# piskac_pan.net
KiCad netlist of a schematic drawn in EAGLE
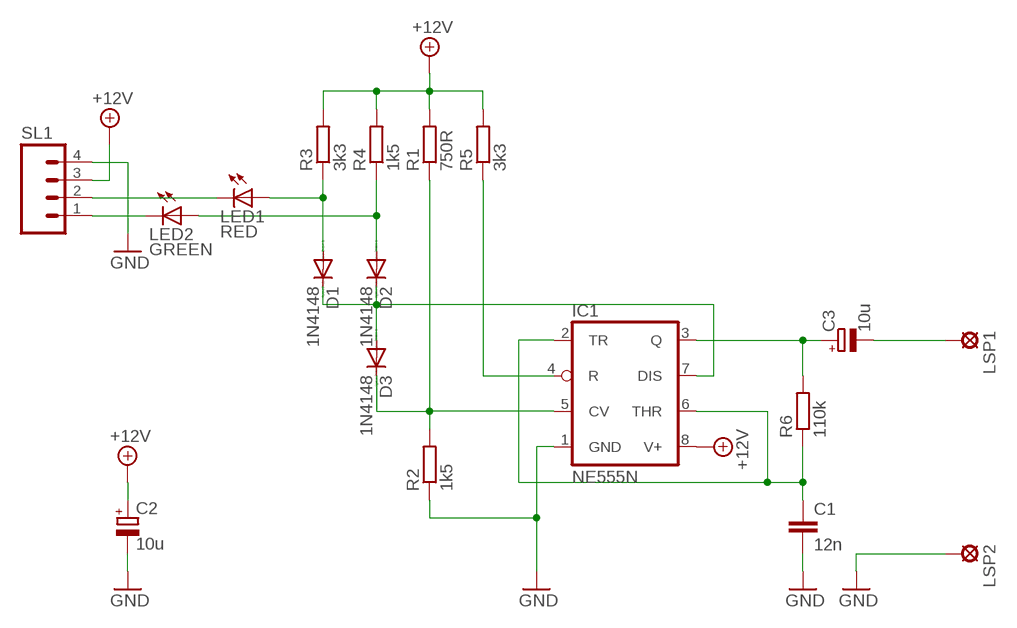
[diagram p0: schematic, sheet 1]

(export (version "E")
  (design (tool "Eeschema 10.0.6"))
  (components
    (comp (ref "C1")
      (value "12n")
      (footprint "eagle-import:C5B3.5")
      (libsource (lib "eagle-import") (part "C5/3.5"))
    )
    (comp (ref "C2")
      (value "10u")
      (footprint "eagle-import:E2,5-6")
      (libsource (lib "eagle-import") (part "CPOL-EUE2.5-6"))
    )
    (comp (ref "C3")
      (value "10u")
      (footprint "eagle-import:E2,5-6")
      (libsource (lib "eagle-import") (part "CPOL-EUE2.5-6"))
    )
    (comp (ref "D1")
      (value "1N4148")
      (footprint "eagle-import:DO35-10")
      (libsource (lib "eagle-import") (part "DIODE-DO35-10"))
    )
    (comp (ref "D2")
      (value "1N4148")
      (footprint "eagle-import:DO35-10")
      (libsource (lib "eagle-import") (part "DIODE-DO35-10"))
    )
    (comp (ref "D3")
      (value "1N4148")
      (footprint "eagle-import:DO35-10")
      (libsource (lib "eagle-import") (part "DIODE-DO35-10"))
    )
    (comp (ref "IC1")
      (value "NE555N")
      (footprint "eagle-import:DIL08")
      (libsource (lib "eagle-import") (part "555NNE"))
    )
    (comp (ref "LED1")
      (value "RED")
      (footprint "eagle-import:LED3MM")
      (libsource (lib "eagle-import") (part "LED3MM"))
    )
    (comp (ref "LED2")
      (value "GREEN")
      (footprint "eagle-import:LED3MM")
      (libsource (lib "eagle-import") (part "LED3MM"))
    )
    (comp (ref "LSP1")
      (value "LSP10")
      (footprint "eagle-import:LSP10")
      (libsource (lib "eagle-import") (part "LSP10"))
    )
    (comp (ref "LSP2")
      (value "LSP10")
      (footprint "eagle-import:LSP10")
      (libsource (lib "eagle-import") (part "LSP10"))
    )
    (comp (ref "R1")
      (value "750R")
      (footprint "eagle-import:0207_10")
      (libsource (lib "eagle-import") (part "R-EU_0207/10"))
    )
    (comp (ref "R2")
      (value "1k5")
      (footprint "eagle-import:0207_10")
      (libsource (lib "eagle-import") (part "R-EU_0207/10"))
    )
    (comp (ref "R3")
      (value "3k3")
      (footprint "eagle-import:0207_10")
      (libsource (lib "eagle-import") (part "R-EU_0207/10"))
    )
    (comp (ref "R4")
      (value "1k5")
      (footprint "eagle-import:0207_10")
      (libsource (lib "eagle-import") (part "R-EU_0207/10"))
    )
    (comp (ref "R5")
      (value "3k3")
      (footprint "eagle-import:0207_10")
      (libsource (lib "eagle-import") (part "R-EU_0207/10"))
    )
    (comp (ref "R6")
      (value "110k")
      (footprint "eagle-import:0207_10")
      (libsource (lib "eagle-import") (part "R-EU_0207/10"))
    )
    (comp (ref "SL1")
      (value "M04")
      (footprint "eagle-import:04P")
      (libsource (lib "eagle-import") (part "M04"))
    )
  )
  (nets
    (net (code "1") (name "+12V") (class "Default")
      (node (ref "C2") (pin "+") (pinfunction "+_+") (pintype "passive"))
      (node (ref "IC1") (pin "8") (pinfunction "V+_8") (pintype "power_in"))
      (node (ref "R1") (pin "2") (pinfunction "2_2") (pintype "passive"))
      (node (ref "R3") (pin "2") (pinfunction "2_2") (pintype "passive"))
      (node (ref "R4") (pin "2") (pinfunction "2_2") (pintype "passive"))
      (node (ref "R5") (pin "2") (pinfunction "2_2") (pintype "passive"))
      (node (ref "SL1") (pin "3") (pinfunction "3_3") (pintype "passive"))
    )
    (net (code "2") (name "GND") (class "Default")
      (node (ref "C1") (pin "2") (pinfunction "2_2") (pintype "passive"))
      (node (ref "C2") (pin "-") (pinfunction "-_-") (pintype "passive"))
      (node (ref "IC1") (pin "1") (pinfunction "GND_1") (pintype "power_in"))
      (node (ref "LSP2") (pin "MP") (pinfunction "MP_MP") (pintype "passive"))
      (node (ref "R2") (pin "1") (pinfunction "1_1") (pintype "passive"))
      (node (ref "SL1") (pin "4") (pinfunction "4_4") (pintype "passive"))
    )
    (net (code "3") (name "Net-(C3-Pad-)") (class "Default")
      (node (ref "C3") (pin "-") (pinfunction "-_-") (pintype "passive"))
      (node (ref "LSP1") (pin "MP") (pinfunction "MP_MP") (pintype "passive"))
    )
    (net (code "4") (name "Net-(D1-PadA)") (class "Default")
      (node (ref "D1") (pin "A") (pinfunction "A_A") (pintype "passive"))
      (node (ref "LED1") (pin "A") (pinfunction "A_A") (pintype "passive"))
      (node (ref "R3") (pin "1") (pinfunction "1_1") (pintype "passive"))
    )
    (net (code "5") (name "Net-(D2-PadA)") (class "Default")
      (node (ref "D2") (pin "A") (pinfunction "A_A") (pintype "passive"))
      (node (ref "LED2") (pin "A") (pinfunction "A_A") (pintype "passive"))
      (node (ref "R4") (pin "1") (pinfunction "1_1") (pintype "passive"))
    )
    (net (code "6") (name "Net-(IC1-CV)") (class "Default")
      (node (ref "D3") (pin "C") (pinfunction "C_C") (pintype "passive"))
      (node (ref "IC1") (pin "5") (pinfunction "CV_5") (pintype "input"))
      (node (ref "R1") (pin "1") (pinfunction "1_1") (pintype "passive"))
      (node (ref "R2") (pin "2") (pinfunction "2_2") (pintype "passive"))
    )
    (net (code "7") (name "Net-(IC1-DIS)") (class "Default")
      (node (ref "D1") (pin "C") (pinfunction "C_C") (pintype "passive"))
      (node (ref "D2") (pin "C") (pinfunction "C_C") (pintype "passive"))
      (node (ref "D3") (pin "A") (pinfunction "A_A") (pintype "passive"))
      (node (ref "IC1") (pin "7") (pinfunction "DIS_7") (pintype "input"))
    )
    (net (code "8") (name "Net-(IC1-Q)") (class "Default")
      (node (ref "C3") (pin "+") (pinfunction "+_+") (pintype "passive"))
      (node (ref "IC1") (pin "3") (pinfunction "Q_3") (pintype "output"))
      (node (ref "R6") (pin "2") (pinfunction "2_2") (pintype "passive"))
    )
    (net (code "9") (name "Net-(IC1-R)") (class "Default")
      (node (ref "IC1") (pin "4") (pinfunction "R_4") (pintype "input"))
      (node (ref "R5") (pin "1") (pinfunction "1_1") (pintype "passive"))
    )
    (net (code "10") (name "Net-(IC1-THR)") (class "Default")
      (node (ref "C1") (pin "1") (pinfunction "1_1") (pintype "passive"))
      (node (ref "IC1") (pin "2") (pinfunction "TR_2") (pintype "input"))
      (node (ref "IC1") (pin "6") (pinfunction "THR_6") (pintype "input"))
      (node (ref "R6") (pin "1") (pinfunction "1_1") (pintype "passive"))
    )
    (net (code "11") (name "Net-(LED1-C)") (class "Default")
      (node (ref "LED1") (pin "K") (pinfunction "C_K") (pintype "passive"))
      (node (ref "SL1") (pin "2") (pinfunction "2_2") (pintype "passive"))
    )
    (net (code "12") (name "Net-(LED2-C)") (class "Default")
      (node (ref "LED2") (pin "K") (pinfunction "C_K") (pintype "passive"))
      (node (ref "SL1") (pin "1") (pinfunction "1_1") (pintype "passive"))
    )
  )
)
